# motor_driver.net
KiCad netlist of a schematic drawn in Altium Designer
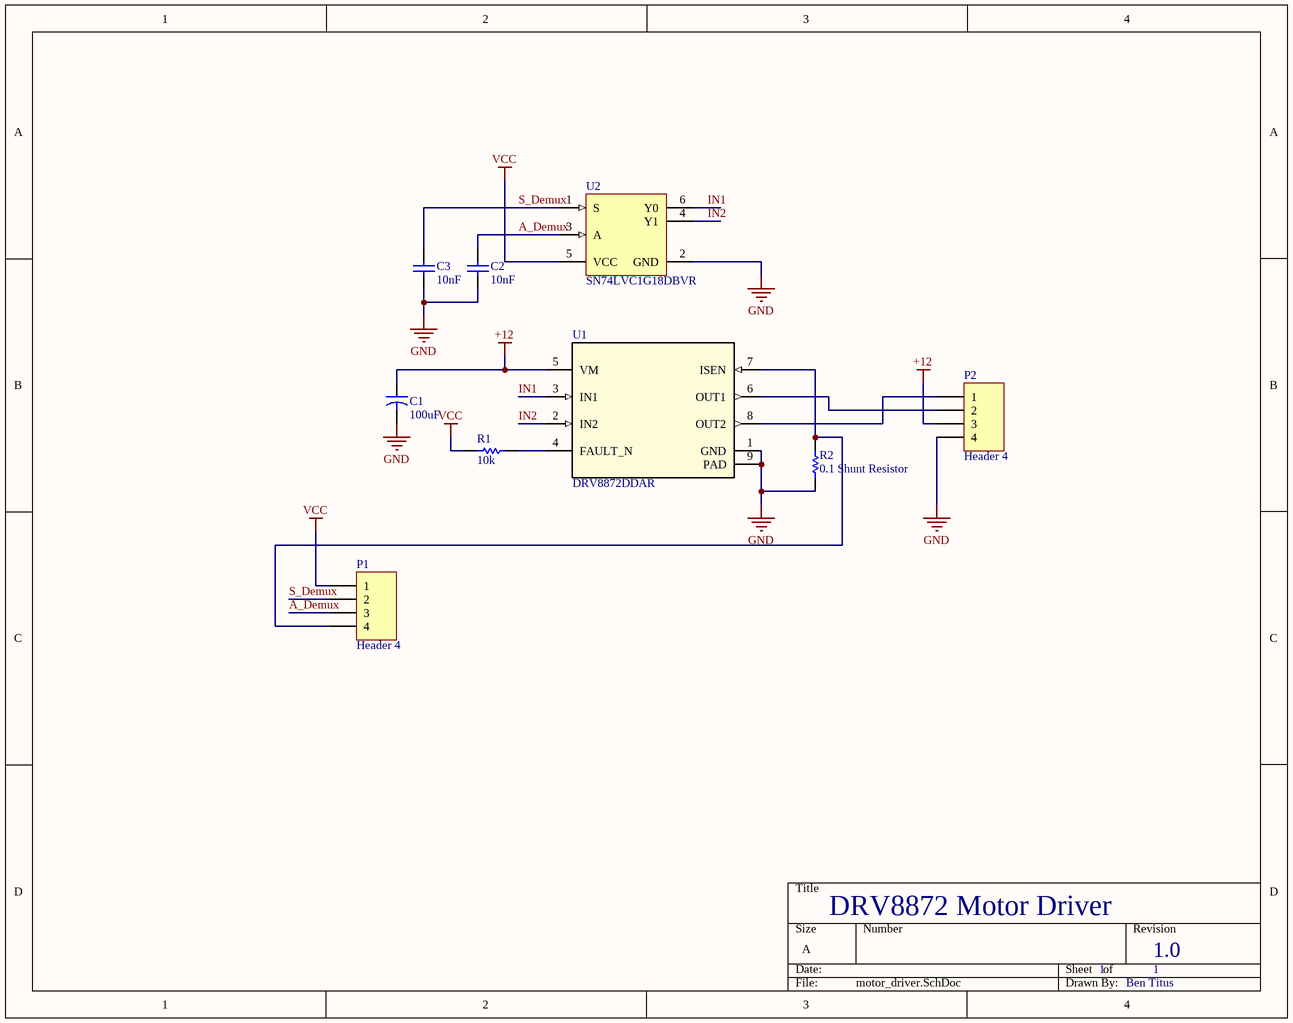
[diagram p0: motor_driver.SchDoc]

(export (version "E")
  (design (tool "Eeschema 10.0.6"))
  (components
    (comp (ref "C1")
      (value "100uF")
      (footprint "CAPR5-4X5")
      (description "Capacitor")
      (fields (field (name "PUBLISHER") "Altium Limited"))
      (libsource (lib "Miscellaneous Devices") (part "Cap2"))
    )
    (comp (ref "C2")
      (value "10nF")
      (footprint "CAPC0805(2012)145_L")
      (description "0805 (2012 Metric) Chip Capacitor")
      (libsource (lib "Altium Content Vault") (part "CAP_5"))
    )
    (comp (ref "C3")
      (value "10nF")
      (footprint "CAPC0805(2012)145_L")
      (description "0805 (2012 Metric) Chip Capacitor")
      (libsource (lib "Altium Content Vault") (part "CAP_5"))
    )
    (comp (ref "P1")
      (value "Header 4")
      (footprint "HDR1X4")
      (description "Header, 4-Pin")
      (fields (field (name "PUBLISHER") "Altium Limited"))
      (libsource (lib "Miscellaneous Connectors") (part "Header 4"))
    )
    (comp (ref "P2")
      (value "Header 4")
      (footprint "HDR1X4")
      (description "Header, 4-Pin")
      (fields (field (name "PUBLISHER") "Altium Limited"))
      (libsource (lib "Miscellaneous Connectors") (part "Header 4"))
    )
    (comp (ref "R1")
      (value "10k")
      (footprint "RESC0805(2012)_L")
      (description "0805 (2012 Metric) Chip Resistor")
      (libsource (lib "Altium Content Vault") (part "RES_3"))
    )
    (comp (ref "R2")
      (value "0.1 Shunt Resistor")
      (footprint "RESC2512(6432)_L")
      (description "2512 (6432 Metric) Chip Resistor")
      (libsource (lib "Altium Content Vault") (part "RES_3"))
    )
    (comp (ref "U1")
      (value "DRV8872DDAR")
      (footprint "DDA0008H_N")
      (description "Imported")
      (fields
        (field (name "ALTERNATE_PARTNUMBER") "DRV8872DDA")
        (field (name "MANUFACTURER") "Texas Instruments")
      )
      (libsource (lib "Custom_Lib") (part "DRV8872DDAR"))
    )
    (comp (ref "U2")
      (value "SN74LVC1G18DBVR")
      (footprint "DBV0006A_L")
      (description "One of Two Noninverting Demultiplexer with 3-State Deselected Output, DBV0006A, LARGE T&R")
      (fields
        (field (name "MANUFACTURER") "Texas Instruments")
        (field (name "GENERIC PART NUMBER") "SN74LVC1G18")
      )
      (libsource (lib "Altium Content Vault") (part "TI-SN74LVC1G18-6"))
    )
  )
  (nets
    (net (code "1") (name "+12") (class "Default")
      (node (ref "C1") (pin "1") (pinfunction "1_1") (pintype "passive"))
      (node (ref "P2") (pin "3") (pinfunction "3_3") (pintype "passive"))
      (node (ref "U1") (pin "5") (pinfunction "VM_5") (pintype "power_in"))
    )
    (net (code "2") (name "/A_Demux") (class "Default")
      (node (ref "C2") (pin "2") (pinfunction "2_2") (pintype "passive"))
      (node (ref "P1") (pin "3") (pinfunction "3_3") (pintype "passive"))
      (node (ref "U2") (pin "3") (pinfunction "A_3") (pintype "input"))
    )
    (net (code "3") (name "/IN1") (class "Default")
      (node (ref "U1") (pin "3") (pinfunction "IN1_3") (pintype "input"))
      (node (ref "U2") (pin "6") (pinfunction "Y0_6") (pintype "tri_state"))
    )
    (net (code "4") (name "/IN2") (class "Default")
      (node (ref "U1") (pin "2") (pinfunction "IN2_2") (pintype "input"))
      (node (ref "U2") (pin "4") (pinfunction "Y1_4") (pintype "tri_state"))
    )
    (net (code "5") (name "/S_Demux") (class "Default")
      (node (ref "C3") (pin "2") (pinfunction "2_2") (pintype "passive"))
      (node (ref "P1") (pin "2") (pinfunction "2_2") (pintype "passive"))
      (node (ref "U2") (pin "1") (pinfunction "S_1") (pintype "input"))
    )
    (net (code "6") (name "GND") (class "Default")
      (node (ref "C1") (pin "2") (pinfunction "2_2") (pintype "passive"))
      (node (ref "C2") (pin "1") (pinfunction "1_1") (pintype "passive"))
      (node (ref "C3") (pin "1") (pinfunction "1_1") (pintype "passive"))
      (node (ref "P2") (pin "4") (pinfunction "4_4") (pintype "passive"))
      (node (ref "R2") (pin "1") (pinfunction "1_1") (pintype "passive"))
      (node (ref "U1") (pin "1") (pinfunction "GND_1") (pintype "power_in"))
      (node (ref "U1") (pin "9") (pinfunction "PAD_9") (pintype "power_in"))
      (node (ref "U2") (pin "2") (pinfunction "GND_2") (pintype "power_in"))
    )
    (net (code "7") (name "Net-(U1-FAULT_N)") (class "Default")
      (node (ref "R1") (pin "2") (pinfunction "2_2") (pintype "passive"))
      (node (ref "U1") (pin "4") (pinfunction "FAULT_N_4") (pintype "open_collector"))
    )
    (net (code "8") (name "Net-(U1-ISEN)") (class "Default")
      (node (ref "P1") (pin "4") (pinfunction "4_4") (pintype "passive"))
      (node (ref "R2") (pin "2") (pinfunction "2_2") (pintype "passive"))
      (node (ref "U1") (pin "7") (pinfunction "ISEN_7") (pintype "input"))
    )
    (net (code "9") (name "Net-(U1-OUT1)") (class "Default")
      (node (ref "P2") (pin "2") (pinfunction "2_2") (pintype "passive"))
      (node (ref "U1") (pin "6") (pinfunction "OUT1_6") (pintype "output"))
    )
    (net (code "10") (name "Net-(U1-OUT2)") (class "Default")
      (node (ref "P2") (pin "1") (pinfunction "1_1") (pintype "passive"))
      (node (ref "U1") (pin "8") (pinfunction "OUT2_8") (pintype "output"))
    )
    (net (code "11") (name "VCC") (class "Default")
      (node (ref "P1") (pin "1") (pinfunction "1_1") (pintype "passive"))
      (node (ref "R1") (pin "1") (pinfunction "1_1") (pintype "passive"))
      (node (ref "U2") (pin "5") (pinfunction "VCC_5") (pintype "power_in"))
    )
  )
)
